# WalkieTalkie_Basic.net
KiCad netlist of a schematic drawn in EAGLE
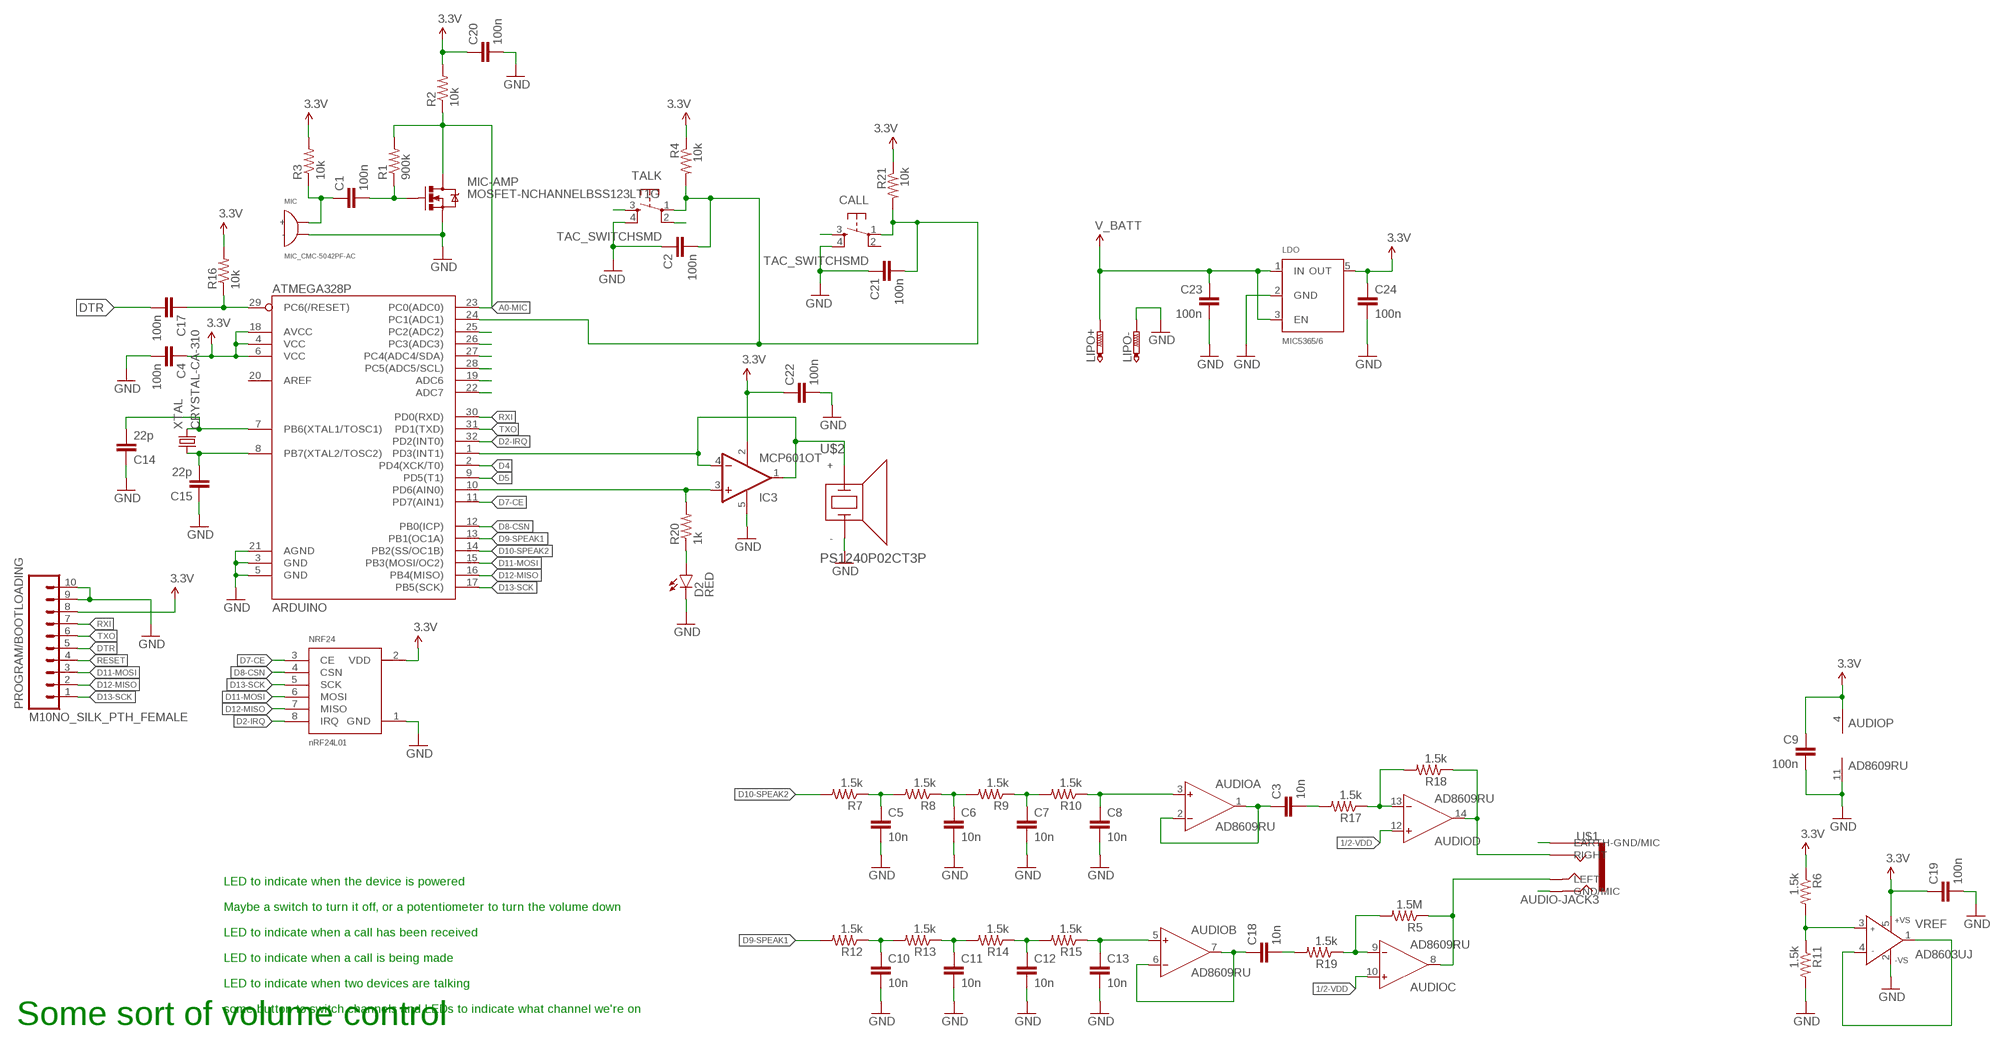
[diagram p0: schematic, sheet 1]

(export (version "E")
  (design (tool "Eeschema 10.0.6"))
  (components
    (comp (ref "ARDUINO")
      (value "ATMEGA328P")
      (footprint "eagle-import:TQFP32-08")
      (libsource (lib "eagle-import") (part "ATMEGA328_SMT-OHMOD"))
    )
    (comp (ref "AUDIO")
      (value "AD8609RU")
      (footprint "eagle-import:TSSOP14")
      (fields (field (name "MF") "ALTERA CORPORATION") (field (name "MPN") "AD8609ARUZ"))
      (libsource (lib "eagle-import") (part "AD8609RU"))
    )
    (comp (ref "C1")
      (value "100n")
      (footprint "eagle-import:C0402")
      (libsource (lib "eagle-import") (part "C-EUC0402"))
    )
    (comp (ref "C2")
      (value "100n")
      (footprint "eagle-import:C0402")
      (libsource (lib "eagle-import") (part "C-EUC0402"))
    )
    (comp (ref "C3")
      (value "10n")
      (footprint "eagle-import:C0402")
      (libsource (lib "eagle-import") (part "C-EUC0402"))
    )
    (comp (ref "C4")
      (value "100n")
      (footprint "eagle-import:C0402")
      (libsource (lib "eagle-import") (part "C-EUC0402"))
    )
    (comp (ref "C5")
      (value "10n")
      (footprint "eagle-import:C0402")
      (libsource (lib "eagle-import") (part "C-EUC0402"))
    )
    (comp (ref "C6")
      (value "10n")
      (footprint "eagle-import:C0402")
      (libsource (lib "eagle-import") (part "C-EUC0402"))
    )
    (comp (ref "C7")
      (value "10n")
      (footprint "eagle-import:C0402")
      (libsource (lib "eagle-import") (part "C-EUC0402"))
    )
    (comp (ref "C8")
      (value "10n")
      (footprint "eagle-import:C0402")
      (libsource (lib "eagle-import") (part "C-EUC0402"))
    )
    (comp (ref "C9")
      (value "100n")
      (footprint "eagle-import:C0402")
      (libsource (lib "eagle-import") (part "C-EUC0402"))
    )
    (comp (ref "C10")
      (value "10n")
      (footprint "eagle-import:C0402")
      (libsource (lib "eagle-import") (part "C-EUC0402"))
    )
    (comp (ref "C11")
      (value "10n")
      (footprint "eagle-import:C0402")
      (libsource (lib "eagle-import") (part "C-EUC0402"))
    )
    (comp (ref "C12")
      (value "10n")
      (footprint "eagle-import:C0402")
      (libsource (lib "eagle-import") (part "C-EUC0402"))
    )
    (comp (ref "C13")
      (value "10n")
      (footprint "eagle-import:C0402")
      (libsource (lib "eagle-import") (part "C-EUC0402"))
    )
    (comp (ref "C14")
      (value "22p")
      (footprint "eagle-import:C0402")
      (libsource (lib "eagle-import") (part "C-EUC0402"))
    )
    (comp (ref "C15")
      (value "22p")
      (footprint "eagle-import:C0402")
      (libsource (lib "eagle-import") (part "C-EUC0402"))
    )
    (comp (ref "C17")
      (value "100n")
      (footprint "eagle-import:C0402")
      (libsource (lib "eagle-import") (part "C-EUC0402"))
    )
    (comp (ref "C18")
      (value "10n")
      (footprint "eagle-import:C0402")
      (libsource (lib "eagle-import") (part "C-EUC0402"))
    )
    (comp (ref "C19")
      (value "100n")
      (footprint "eagle-import:C0402")
      (libsource (lib "eagle-import") (part "C-EUC0402"))
    )
    (comp (ref "C20")
      (value "100n")
      (footprint "eagle-import:C0402")
      (libsource (lib "eagle-import") (part "C-EUC0402"))
    )
    (comp (ref "C21")
      (value "100n")
      (footprint "eagle-import:C0402")
      (libsource (lib "eagle-import") (part "C-EUC0402"))
    )
    (comp (ref "C22")
      (value "100n")
      (footprint "eagle-import:C0402")
      (libsource (lib "eagle-import") (part "C-EUC0402"))
    )
    (comp (ref "C23")
      (value "100n")
      (footprint "eagle-import:C0402")
      (libsource (lib "eagle-import") (part "C-EUC0402"))
    )
    (comp (ref "C24")
      (value "100n")
      (footprint "eagle-import:C0402")
      (libsource (lib "eagle-import") (part "C-EUC0402"))
    )
    (comp (ref "CALL")
      (value "TAC_SWITCHSMD")
      (footprint "eagle-import:TACTILE-SWITCH-SMD")
      (libsource (lib "eagle-import") (part "TAC_SWITCHSMD"))
    )
    (comp (ref "D2")
      (value "RED")
      (footprint "eagle-import:LED-0603")
      (libsource (lib "eagle-import") (part "LED-RED0603"))
    )
    (comp (ref "IC3")
      (value "MCP601OT")
      (footprint "eagle-import:SOT23-5")
      (libsource (lib "eagle-import") (part "MCP601OT"))
    )
    (comp (ref "LDO")
      (value "MIC5365/6")
      (footprint "eagle-import:SC-70-5")
      (libsource (lib "eagle-import") (part "MIC5365/6"))
    )
    (comp (ref "LIPO")
      (value "BATT-CONNECT")
      (footprint "eagle-import:HOLE")
      (libsource (lib "eagle-import") (part "BATT-CONNECT"))
    )
    (comp (ref "MIC")
      (value "MIC_CMC-5042PF-AC")
      (footprint "eagle-import:MIC_01")
      (libsource (lib "eagle-import") (part "MIC_CMC-5042PF-AC"))
    )
    (comp (ref "MIC-AMP")
      (value "MOSFET-NCHANNELBSS123LT1G")
      (footprint "eagle-import:SOT23-3")
      (libsource (lib "eagle-import") (part "MOSFET-NCHANNELBSS123LT1G"))
    )
    (comp (ref "NRF24")
      (value "NRF24L01-BREAKOUT")
      (footprint "eagle-import:NRF24L01-BREAKOUT")
      (libsource (lib "eagle-import") (part "NRF24L01-BREAKOUT"))
    )
    (comp (ref "PROGRAM/BOOTLOADING")
      (value "M10NO_SILK_PTH_FEMALE")
      (footprint "eagle-import:1X10_NO_SILK")
      (libsource (lib "eagle-import") (part "M10NO_SILK_PTH_FEMALE"))
    )
    (comp (ref "R1")
      (value "900k")
      (footprint "eagle-import:R0402")
      (libsource (lib "eagle-import") (part "R-US_R0402"))
    )
    (comp (ref "R2")
      (value "10k")
      (footprint "eagle-import:R0402")
      (libsource (lib "eagle-import") (part "R-US_R0402"))
    )
    (comp (ref "R3")
      (value "10k")
      (footprint "eagle-import:R0402")
      (libsource (lib "eagle-import") (part "R-US_R0402"))
    )
    (comp (ref "R4")
      (value "10k")
      (footprint "eagle-import:R0402")
      (libsource (lib "eagle-import") (part "R-US_R0402"))
    )
    (comp (ref "R5")
      (value "1.5M")
      (footprint "eagle-import:R0402")
      (libsource (lib "eagle-import") (part "R-US_R0402"))
    )
    (comp (ref "R6")
      (value "1.5k")
      (footprint "eagle-import:R0402")
      (libsource (lib "eagle-import") (part "R-US_R0402"))
    )
    (comp (ref "R7")
      (value "1.5k")
      (footprint "eagle-import:R0402")
      (libsource (lib "eagle-import") (part "R-US_R0402"))
    )
    (comp (ref "R8")
      (value "1.5k")
      (footprint "eagle-import:R0402")
      (libsource (lib "eagle-import") (part "R-US_R0402"))
    )
    (comp (ref "R9")
      (value "1.5k")
      (footprint "eagle-import:R0402")
      (libsource (lib "eagle-import") (part "R-US_R0402"))
    )
    (comp (ref "R10")
      (value "1.5k")
      (footprint "eagle-import:R0402")
      (libsource (lib "eagle-import") (part "R-US_R0402"))
    )
    (comp (ref "R11")
      (value "1.5k")
      (footprint "eagle-import:R0402")
      (libsource (lib "eagle-import") (part "R-US_R0402"))
    )
    (comp (ref "R12")
      (value "1.5k")
      (footprint "eagle-import:R0402")
      (libsource (lib "eagle-import") (part "R-US_R0402"))
    )
    (comp (ref "R13")
      (value "1.5k")
      (footprint "eagle-import:R0402")
      (libsource (lib "eagle-import") (part "R-US_R0402"))
    )
    (comp (ref "R14")
      (value "1.5k")
      (footprint "eagle-import:R0402")
      (libsource (lib "eagle-import") (part "R-US_R0402"))
    )
    (comp (ref "R15")
      (value "1.5k")
      (footprint "eagle-import:R0402")
      (libsource (lib "eagle-import") (part "R-US_R0402"))
    )
    (comp (ref "R16")
      (value "10k")
      (footprint "eagle-import:R0402")
      (libsource (lib "eagle-import") (part "R-US_R0402"))
    )
    (comp (ref "R17")
      (value "1.5k")
      (footprint "eagle-import:R0402")
      (libsource (lib "eagle-import") (part "R-US_R0402"))
    )
    (comp (ref "R18")
      (value "1.5k")
      (footprint "eagle-import:R0402")
      (libsource (lib "eagle-import") (part "R-US_R0402"))
    )
    (comp (ref "R19")
      (value "1.5k")
      (footprint "eagle-import:R0402")
      (libsource (lib "eagle-import") (part "R-US_R0402"))
    )
    (comp (ref "R20")
      (value "1k")
      (footprint "eagle-import:R0402")
      (libsource (lib "eagle-import") (part "R-US_R0402"))
    )
    (comp (ref "R21")
      (value "10k")
      (footprint "eagle-import:R0402")
      (libsource (lib "eagle-import") (part "R-US_R0402"))
    )
    (comp (ref "TALK")
      (value "TAC_SWITCHSMD")
      (footprint "eagle-import:TACTILE-SWITCH-SMD")
      (libsource (lib "eagle-import") (part "TAC_SWITCHSMD"))
    )
    (comp (ref "U$1")
      (value "AUDIO-JACK3")
      (footprint "eagle-import:AUDIO-JACK-TRRS-SMD")
      (libsource (lib "eagle-import") (part "AUDIO-JACK3"))
    )
    (comp (ref "U$2")
      (value "PS1240P02CT3P")
      (footprint "eagle-import:PIEZO-1")
      (libsource (lib "eagle-import") (part "PS1240P02CT3P"))
    )
    (comp (ref "VREF")
      (value "AD8603UJ")
      (footprint "eagle-import:SOT23-5")
      (fields (field (name "MF") "ALTERA CORPORATION") (field (name "MPN") "AD8603AUJZ-REEL7"))
      (libsource (lib "eagle-import") (part "AD8603UJ"))
    )
    (comp (ref "XTAL")
      (value "CRYSTAL-CA-310")
      (footprint "eagle-import:CA-301")
      (libsource (lib "eagle-import") (part "CRYSTAL-CA-310"))
    )
  )
  (nets
    (net (code "1") (name "1{slash}2-VDD") (class "Default")
      (node (ref "AUDIO") (pin "10") (pinfunction "IN+_10") (pintype "input"))
      (node (ref "AUDIO") (pin "12") (pinfunction "IN+_12") (pintype "input"))
      (node (ref "VREF") (pin "1") (pinfunction "OUT_1") (pintype "output"))
      (node (ref "VREF") (pin "4") (pinfunction "IN-_4") (pintype "input"))
    )
    (net (code "2") (name "3.3V") (class "Default")
      (node (ref "ARDUINO") (pin "18") (pinfunction "AVCC_18") (pintype "bidirectional"))
      (node (ref "ARDUINO") (pin "4") (pinfunction "VCC_4") (pintype "bidirectional"))
      (node (ref "ARDUINO") (pin "6") (pinfunction "VCC_6") (pintype "bidirectional"))
      (node (ref "AUDIO") (pin "4") (pinfunction "V+_4") (pintype "power_in"))
      (node (ref "C19") (pin "1") (pinfunction "1_1") (pintype "passive"))
      (node (ref "C20") (pin "1") (pinfunction "1_1") (pintype "passive"))
      (node (ref "C22") (pin "1") (pinfunction "1_1") (pintype "passive"))
      (node (ref "C24") (pin "1") (pinfunction "1_1") (pintype "passive"))
      (node (ref "C4") (pin "1") (pinfunction "1_1") (pintype "passive"))
      (node (ref "C9") (pin "1") (pinfunction "1_1") (pintype "passive"))
      (node (ref "IC3") (pin "2") (pinfunction "V-_2") (pintype "power_in"))
      (node (ref "LDO") (pin "5") (pinfunction "OUT_5") (pintype "bidirectional"))
      (node (ref "NRF24") (pin "2") (pinfunction "VDD_2") (pintype "bidirectional"))
      (node (ref "PROGRAM/BOOTLOADING") (pin "8") (pinfunction "8_8") (pintype "passive"))
      (node (ref "R16") (pin "2") (pinfunction "2_2") (pintype "passive"))
      (node (ref "R2") (pin "2") (pinfunction "2_2") (pintype "passive"))
      (node (ref "R21") (pin "1") (pinfunction "1_1") (pintype "passive"))
      (node (ref "R3") (pin "2") (pinfunction "2_2") (pintype "passive"))
      (node (ref "R4") (pin "1") (pinfunction "1_1") (pintype "passive"))
      (node (ref "R6") (pin "1") (pinfunction "1_1") (pintype "passive"))
      (node (ref "VREF") (pin "5") (pinfunction "+VS_5") (pintype "input"))
    )
    (net (code "3") (name "A0-MIC") (class "Default")
      (node (ref "ARDUINO") (pin "23") (pinfunction "PC0(ADC0)_23") (pintype "bidirectional"))
      (node (ref "MIC-AMP") (pin "3") (pinfunction "D_3") (pintype "passive"))
      (node (ref "R1") (pin "2") (pinfunction "2_2") (pintype "passive"))
      (node (ref "R2") (pin "1") (pinfunction "1_1") (pintype "passive"))
    )
    (net (code "4") (name "D2-IRQ") (class "Default")
      (node (ref "ARDUINO") (pin "32") (pinfunction "PD2(INT0)_32") (pintype "bidirectional"))
      (node (ref "NRF24") (pin "8") (pinfunction "IRQ_8") (pintype "bidirectional"))
    )
    (net (code "5") (name "D4") (class "Default")
      (node (ref "ARDUINO") (pin "2") (pinfunction "PD4(XCK/T0)_2") (pintype "bidirectional"))
    )
    (net (code "6") (name "D5") (class "Default")
      (node (ref "ARDUINO") (pin "9") (pinfunction "PD5(T1)_9") (pintype "bidirectional"))
    )
    (net (code "7") (name "D7-CE") (class "Default")
      (node (ref "ARDUINO") (pin "11") (pinfunction "PD7(AIN1)_11") (pintype "bidirectional"))
      (node (ref "NRF24") (pin "3") (pinfunction "CE_3") (pintype "bidirectional"))
    )
    (net (code "8") (name "D8-CSN") (class "Default")
      (node (ref "ARDUINO") (pin "12") (pinfunction "PB0(ICP)_12") (pintype "bidirectional"))
      (node (ref "NRF24") (pin "4") (pinfunction "CSN_4") (pintype "bidirectional"))
    )
    (net (code "9") (name "D9-SPEAK1") (class "Default")
      (node (ref "ARDUINO") (pin "13") (pinfunction "PB1(OC1A)_13") (pintype "bidirectional"))
      (node (ref "R12") (pin "2") (pinfunction "2_2") (pintype "passive"))
    )
    (net (code "10") (name "D10-SPEAK2") (class "Default")
      (node (ref "ARDUINO") (pin "14") (pinfunction "PB2(SS/OC1B)_14") (pintype "bidirectional"))
      (node (ref "R7") (pin "2") (pinfunction "2_2") (pintype "passive"))
    )
    (net (code "11") (name "D11-MOSI") (class "Default")
      (node (ref "ARDUINO") (pin "15") (pinfunction "PB3(MOSI/OC2)_15") (pintype "bidirectional"))
      (node (ref "NRF24") (pin "6") (pinfunction "MOSI_6") (pintype "bidirectional"))
      (node (ref "PROGRAM/BOOTLOADING") (pin "3") (pinfunction "3_3") (pintype "passive"))
    )
    (net (code "12") (name "D12-MISO") (class "Default")
      (node (ref "ARDUINO") (pin "16") (pinfunction "PB4(MISO)_16") (pintype "bidirectional"))
      (node (ref "NRF24") (pin "7") (pinfunction "MISO_7") (pintype "bidirectional"))
      (node (ref "PROGRAM/BOOTLOADING") (pin "2") (pinfunction "2_2") (pintype "passive"))
    )
    (net (code "13") (name "D13-SCK") (class "Default")
      (node (ref "ARDUINO") (pin "17") (pinfunction "PB5(SCK)_17") (pintype "bidirectional"))
      (node (ref "NRF24") (pin "5") (pinfunction "SCK_5") (pintype "bidirectional"))
      (node (ref "PROGRAM/BOOTLOADING") (pin "1") (pinfunction "1_1") (pintype "passive"))
    )
    (net (code "14") (name "DTR") (class "Default")
      (node (ref "C17") (pin "2") (pinfunction "2_2") (pintype "passive"))
      (node (ref "PROGRAM/BOOTLOADING") (pin "5") (pinfunction "5_5") (pintype "passive"))
    )
    (net (code "15") (name "GND") (class "Default")
      (node (ref "ARDUINO") (pin "21") (pinfunction "AGND_21") (pintype "bidirectional"))
      (node (ref "ARDUINO") (pin "3") (pinfunction "GND_3") (pintype "bidirectional"))
      (node (ref "ARDUINO") (pin "5") (pinfunction "GND_5") (pintype "bidirectional"))
      (node (ref "AUDIO") (pin "11") (pinfunction "V-_11") (pintype "power_in"))
      (node (ref "C10") (pin "2") (pinfunction "2_2") (pintype "passive"))
      (node (ref "C11") (pin "2") (pinfunction "2_2") (pintype "passive"))
      (node (ref "C12") (pin "2") (pinfunction "2_2") (pintype "passive"))
      (node (ref "C13") (pin "2") (pinfunction "2_2") (pintype "passive"))
      (node (ref "C14") (pin "1") (pinfunction "1_1") (pintype "passive"))
      (node (ref "C15") (pin "1") (pinfunction "1_1") (pintype "passive"))
      (node (ref "C19") (pin "2") (pinfunction "2_2") (pintype "passive"))
      (node (ref "C2") (pin "1") (pinfunction "1_1") (pintype "passive"))
      (node (ref "C20") (pin "2") (pinfunction "2_2") (pintype "passive"))
      (node (ref "C21") (pin "1") (pinfunction "1_1") (pintype "passive"))
      (node (ref "C22") (pin "2") (pinfunction "2_2") (pintype "passive"))
      (node (ref "C23") (pin "2") (pinfunction "2_2") (pintype "passive"))
      (node (ref "C24") (pin "2") (pinfunction "2_2") (pintype "passive"))
      (node (ref "C4") (pin "2") (pinfunction "2_2") (pintype "passive"))
      (node (ref "C5") (pin "2") (pinfunction "2_2") (pintype "passive"))
      (node (ref "C6") (pin "2") (pinfunction "2_2") (pintype "passive"))
      (node (ref "C7") (pin "2") (pinfunction "2_2") (pintype "passive"))
      (node (ref "C8") (pin "2") (pinfunction "2_2") (pintype "passive"))
      (node (ref "C9") (pin "2") (pinfunction "2_2") (pintype "passive"))
      (node (ref "CALL") (pin "4") (pinfunction "4_4") (pintype "passive"))
      (node (ref "D2") (pin "C") (pinfunction "C_C") (pintype "passive"))
      (node (ref "IC3") (pin "5") (pinfunction "V+_5") (pintype "power_in"))
      (node (ref "LDO") (pin "2") (pinfunction "GND_2") (pintype "bidirectional"))
      (node (ref "LIPO") (pin "P$2") (pinfunction "TP_P$2") (pintype "input"))
      (node (ref "MIC") (pin "-") (pinfunction "-_-") (pintype "bidirectional"))
      (node (ref "MIC-AMP") (pin "2") (pinfunction "S_2") (pintype "passive"))
      (node (ref "NRF24") (pin "1") (pinfunction "GND_1") (pintype "bidirectional"))
      (node (ref "PROGRAM/BOOTLOADING") (pin "10") (pinfunction "10_10") (pintype "passive"))
      (node (ref "PROGRAM/BOOTLOADING") (pin "9") (pinfunction "9_9") (pintype "passive"))
      (node (ref "R11") (pin "2") (pinfunction "2_2") (pintype "passive"))
      (node (ref "TALK") (pin "4") (pinfunction "4_4") (pintype "passive"))
      (node (ref "U$2") (pin "-") (pinfunction "-_-") (pintype "bidirectional"))
      (node (ref "VREF") (pin "2") (pinfunction "-VS_2") (pintype "input"))
    )
    (net (code "16") (name "Net-(ARDUINO-PB6(XTAL1{slash}TOSC1))") (class "Default")
      (node (ref "ARDUINO") (pin "7") (pinfunction "PB6(XTAL1/TOSC1)_7") (pintype "bidirectional"))
      (node (ref "C14") (pin "2") (pinfunction "2_2") (pintype "passive"))
      (node (ref "XTAL") (pin "2") (pinfunction "2_2") (pintype "passive"))
    )
    (net (code "17") (name "Net-(ARDUINO-PB7(XTAL2{slash}TOSC2))") (class "Default")
      (node (ref "ARDUINO") (pin "8") (pinfunction "PB7(XTAL2/TOSC2)_8") (pintype "bidirectional"))
      (node (ref "C15") (pin "2") (pinfunction "2_2") (pintype "passive"))
      (node (ref "XTAL") (pin "1") (pinfunction "1_1") (pintype "passive"))
    )
    (net (code "18") (name "Net-(ARDUINO-PC1(ADC1))") (class "Default")
      (node (ref "ARDUINO") (pin "24") (pinfunction "PC1(ADC1)_24") (pintype "bidirectional"))
      (node (ref "C2") (pin "2") (pinfunction "2_2") (pintype "passive"))
      (node (ref "C21") (pin "2") (pinfunction "2_2") (pintype "passive"))
      (node (ref "CALL") (pin "1") (pinfunction "1_1") (pintype "passive"))
      (node (ref "R21") (pin "2") (pinfunction "2_2") (pintype "passive"))
      (node (ref "R4") (pin "2") (pinfunction "2_2") (pintype "passive"))
      (node (ref "TALK") (pin "1") (pinfunction "1_1") (pintype "passive"))
    )
    (net (code "19") (name "Net-(ARDUINO-PD3(INT1))") (class "Default")
      (node (ref "ARDUINO") (pin "1") (pinfunction "PD3(INT1)_1") (pintype "bidirectional"))
      (node (ref "IC3") (pin "1") (pinfunction "OUT_1") (pintype "output"))
      (node (ref "IC3") (pin "4") (pinfunction "-IN_4") (pintype "input"))
      (node (ref "U$2") (pin "+") (pinfunction "+_+") (pintype "bidirectional"))
    )
    (net (code "20") (name "Net-(ARDUINO-PD6(AIN0))") (class "Default")
      (node (ref "ARDUINO") (pin "10") (pinfunction "PD6(AIN0)_10") (pintype "bidirectional"))
      (node (ref "IC3") (pin "3") (pinfunction "+IN_3") (pintype "input"))
      (node (ref "R20") (pin "2") (pinfunction "2_2") (pintype "passive"))
    )
    (net (code "21") (name "Net-(AUDIOA-IN+)") (class "Default")
      (node (ref "AUDIO") (pin "3") (pinfunction "IN+_3") (pintype "input"))
      (node (ref "C8") (pin "1") (pinfunction "1_1") (pintype "passive"))
      (node (ref "R10") (pin "1") (pinfunction "1_1") (pintype "passive"))
    )
    (net (code "22") (name "Net-(AUDIOA-IN-)") (class "Default")
      (node (ref "AUDIO") (pin "1") (pinfunction "OUT_1") (pintype "output"))
      (node (ref "AUDIO") (pin "2") (pinfunction "IN-_2") (pintype "input"))
      (node (ref "C3") (pin "1") (pinfunction "1_1") (pintype "passive"))
    )
    (net (code "23") (name "Net-(AUDIOB-IN+)") (class "Default")
      (node (ref "AUDIO") (pin "5") (pinfunction "IN+_5") (pintype "input"))
      (node (ref "C13") (pin "1") (pinfunction "1_1") (pintype "passive"))
      (node (ref "R15") (pin "1") (pinfunction "1_1") (pintype "passive"))
    )
    (net (code "24") (name "Net-(AUDIOB-IN-)") (class "Default")
      (node (ref "AUDIO") (pin "6") (pinfunction "IN-_6") (pintype "input"))
      (node (ref "AUDIO") (pin "7") (pinfunction "OUT_7") (pintype "output"))
      (node (ref "C18") (pin "1") (pinfunction "1_1") (pintype "passive"))
    )
    (net (code "25") (name "Net-(AUDIOC-IN-)") (class "Default")
      (node (ref "AUDIO") (pin "9") (pinfunction "IN-_9") (pintype "input"))
      (node (ref "R19") (pin "1") (pinfunction "1_1") (pintype "passive"))
      (node (ref "R5") (pin "2") (pinfunction "2_2") (pintype "passive"))
    )
    (net (code "26") (name "Net-(AUDIOC-OUT)") (class "Default")
      (node (ref "AUDIO") (pin "8") (pinfunction "OUT_8") (pintype "output"))
      (node (ref "R5") (pin "1") (pinfunction "1_1") (pintype "passive"))
      (node (ref "U$1") (pin "TIP") (pinfunction "LEFT_TIP") (pintype "bidirectional"))
    )
    (net (code "27") (name "Net-(AUDIOD-IN-)") (class "Default")
      (node (ref "AUDIO") (pin "13") (pinfunction "IN-_13") (pintype "input"))
      (node (ref "R17") (pin "1") (pinfunction "1_1") (pintype "passive"))
      (node (ref "R18") (pin "2") (pinfunction "2_2") (pintype "passive"))
    )
    (net (code "28") (name "Net-(AUDIOD-OUT)") (class "Default")
      (node (ref "AUDIO") (pin "14") (pinfunction "OUT_14") (pintype "output"))
      (node (ref "R18") (pin "1") (pinfunction "1_1") (pintype "passive"))
      (node (ref "U$1") (pin "RING1") (pinfunction "RIGHT_RING1") (pintype "bidirectional"))
    )
    (net (code "29") (name "Net-(C1-Pad1)") (class "Default")
      (node (ref "C1") (pin "1") (pinfunction "1_1") (pintype "passive"))
      (node (ref "MIC") (pin "+") (pinfunction "+_+") (pintype "bidirectional"))
      (node (ref "R3") (pin "1") (pinfunction "1_1") (pintype "passive"))
    )
    (net (code "30") (name "Net-(C3-Pad2)") (class "Default")
      (node (ref "C3") (pin "2") (pinfunction "2_2") (pintype "passive"))
      (node (ref "R17") (pin "2") (pinfunction "2_2") (pintype "passive"))
    )
    (net (code "31") (name "Net-(C5-Pad1)") (class "Default")
      (node (ref "C5") (pin "1") (pinfunction "1_1") (pintype "passive"))
      (node (ref "R7") (pin "1") (pinfunction "1_1") (pintype "passive"))
      (node (ref "R8") (pin "2") (pinfunction "2_2") (pintype "passive"))
    )
    (net (code "32") (name "Net-(C6-Pad1)") (class "Default")
      (node (ref "C6") (pin "1") (pinfunction "1_1") (pintype "passive"))
      (node (ref "R8") (pin "1") (pinfunction "1_1") (pintype "passive"))
      (node (ref "R9") (pin "2") (pinfunction "2_2") (pintype "passive"))
    )
    (net (code "33") (name "Net-(C7-Pad1)") (class "Default")
      (node (ref "C7") (pin "1") (pinfunction "1_1") (pintype "passive"))
      (node (ref "R10") (pin "2") (pinfunction "2_2") (pintype "passive"))
      (node (ref "R9") (pin "1") (pinfunction "1_1") (pintype "passive"))
    )
    (net (code "34") (name "Net-(C10-Pad1)") (class "Default")
      (node (ref "C10") (pin "1") (pinfunction "1_1") (pintype "passive"))
      (node (ref "R12") (pin "1") (pinfunction "1_1") (pintype "passive"))
      (node (ref "R13") (pin "2") (pinfunction "2_2") (pintype "passive"))
    )
    (net (code "35") (name "Net-(C11-Pad1)") (class "Default")
      (node (ref "C11") (pin "1") (pinfunction "1_1") (pintype "passive"))
      (node (ref "R13") (pin "1") (pinfunction "1_1") (pintype "passive"))
      (node (ref "R14") (pin "2") (pinfunction "2_2") (pintype "passive"))
    )
    (net (code "36") (name "Net-(C12-Pad1)") (class "Default")
      (node (ref "C12") (pin "1") (pinfunction "1_1") (pintype "passive"))
      (node (ref "R14") (pin "1") (pinfunction "1_1") (pintype "passive"))
      (node (ref "R15") (pin "2") (pinfunction "2_2") (pintype "passive"))
    )
    (net (code "37") (name "Net-(C18-Pad2)") (class "Default")
      (node (ref "C18") (pin "2") (pinfunction "2_2") (pintype "passive"))
      (node (ref "R19") (pin "2") (pinfunction "2_2") (pintype "passive"))
    )
    (net (code "38") (name "Net-(D2-PadA)") (class "Default")
      (node (ref "D2") (pin "A") (pinfunction "A_A") (pintype "passive"))
      (node (ref "R20") (pin "1") (pinfunction "1_1") (pintype "passive"))
    )
    (net (code "39") (name "Net-(MIC-AMP-G)") (class "Default")
      (node (ref "C1") (pin "2") (pinfunction "2_2") (pintype "passive"))
      (node (ref "MIC-AMP") (pin "1") (pinfunction "G_1") (pintype "passive"))
      (node (ref "R1") (pin "1") (pinfunction "1_1") (pintype "passive"))
    )
    (net (code "40") (name "Net-(VREF-IN+)") (class "Default")
      (node (ref "R11") (pin "1") (pinfunction "1_1") (pintype "passive"))
      (node (ref "R6") (pin "2") (pinfunction "2_2") (pintype "passive"))
      (node (ref "VREF") (pin "3") (pinfunction "IN+_3") (pintype "input"))
    )
    (net (code "41") (name "RESET") (class "Default")
      (node (ref "ARDUINO") (pin "29") (pinfunction "PC6(/RESET)_29") (pintype "bidirectional"))
      (node (ref "C17") (pin "1") (pinfunction "1_1") (pintype "passive"))
      (node (ref "PROGRAM/BOOTLOADING") (pin "4") (pinfunction "4_4") (pintype "passive"))
      (node (ref "R16") (pin "1") (pinfunction "1_1") (pintype "passive"))
    )
    (net (code "42") (name "RXI") (class "Default")
      (node (ref "ARDUINO") (pin "30") (pinfunction "PD0(RXD)_30") (pintype "bidirectional"))
      (node (ref "PROGRAM/BOOTLOADING") (pin "7") (pinfunction "7_7") (pintype "passive"))
    )
    (net (code "43") (name "TXO") (class "Default")
      (node (ref "ARDUINO") (pin "31") (pinfunction "PD1(TXD)_31") (pintype "bidirectional"))
      (node (ref "PROGRAM/BOOTLOADING") (pin "6") (pinfunction "6_6") (pintype "passive"))
    )
    (net (code "44") (name "V_BATT") (class "Default")
      (node (ref "C23") (pin "1") (pinfunction "1_1") (pintype "passive"))
      (node (ref "LDO") (pin "1") (pinfunction "IN_1") (pintype "bidirectional"))
      (node (ref "LDO") (pin "3") (pinfunction "EN_3") (pintype "bidirectional"))
      (node (ref "LIPO") (pin "P$1") (pinfunction "TP_P$1") (pintype "input"))
    )
    (net (code "45") (name "unconnected-(ARDUINO-ADC6-Pad19)") (class "Default")
      (node (ref "ARDUINO") (pin "19") (pinfunction "ADC6_19") (pintype "bidirectional"))
    )
    (net (code "46") (name "unconnected-(ARDUINO-ADC7-Pad22)") (class "Default")
      (node (ref "ARDUINO") (pin "22") (pinfunction "ADC7_22") (pintype "bidirectional"))
    )
    (net (code "47") (name "unconnected-(ARDUINO-AREF-Pad20)") (class "Default")
      (node (ref "ARDUINO") (pin "20") (pinfunction "AREF_20") (pintype "bidirectional"))
    )
    (net (code "48") (name "unconnected-(ARDUINO-PC2(ADC2)-Pad25)") (class "Default")
      (node (ref "ARDUINO") (pin "25") (pinfunction "PC2(ADC2)_25") (pintype "bidirectional"))
    )
    (net (code "49") (name "unconnected-(ARDUINO-PC3(ADC3)-Pad26)") (class "Default")
      (node (ref "ARDUINO") (pin "26") (pinfunction "PC3(ADC3)_26") (pintype "bidirectional"))
    )
    (net (code "50") (name "unconnected-(ARDUINO-PC4(ADC4{slash}SDA)-Pad27)") (class "Default")
      (node (ref "ARDUINO") (pin "27") (pinfunction "PC4(ADC4/SDA)_27") (pintype "bidirectional"))
    )
    (net (code "51") (name "unconnected-(ARDUINO-PC5(ADC5{slash}SCL)-Pad28)") (class "Default")
      (node (ref "ARDUINO") (pin "28") (pinfunction "PC5(ADC5/SCL)_28") (pintype "bidirectional"))
    )
    (net (code "52") (name "unconnected-(CALL-Pad2)") (class "Default")
      (node (ref "CALL") (pin "2") (pinfunction "2_2") (pintype "passive"))
    )
    (net (code "53") (name "unconnected-(CALL-Pad3)") (class "Default")
      (node (ref "CALL") (pin "3") (pinfunction "3_3") (pintype "passive"))
    )
    (net (code "54") (name "unconnected-(TALK-Pad2)") (class "Default")
      (node (ref "TALK") (pin "2") (pinfunction "2_2") (pintype "passive"))
    )
    (net (code "55") (name "unconnected-(TALK-Pad3)") (class "Default")
      (node (ref "TALK") (pin "3") (pinfunction "3_3") (pintype "passive"))
    )
    (net (code "56") (name "unconnected-(U$1-EARTH-GND{slash}MIC-PadEARTH)") (class "Default")
      (node (ref "U$1") (pin "EARTH") (pinfunction "EARTH-GND/MIC_EARTH") (pintype "bidirectional"))
    )
    (net (code "57") (name "unconnected-(U$1-GND{slash}MIC-PadRING2)") (class "Default")
      (node (ref "U$1") (pin "RING2") (pinfunction "GND/MIC_RING2") (pintype "bidirectional"))
    )
  )
)
